# board_Two.net
KiCad netlist of a schematic drawn in Altium Designer
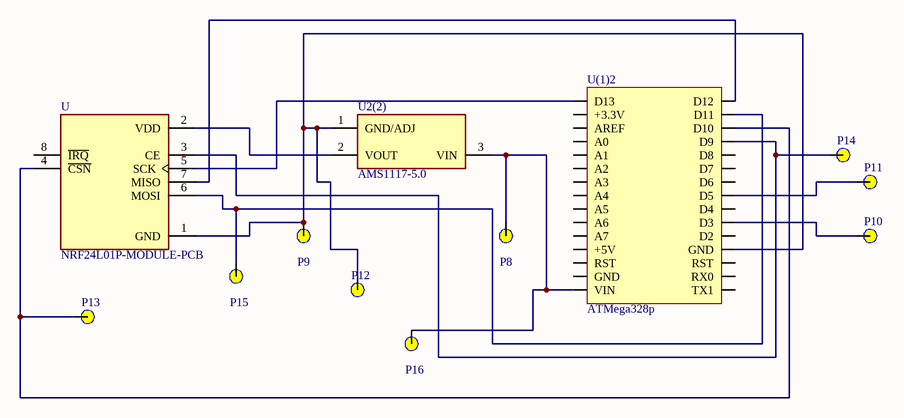
[diagram p0: board_Two.SchDoc]

(export (version "E")
  (design (tool "Eeschema 10.0.6"))
  (components
    (comp (ref "P8") (value "PIN_1") (footprint "PCB_Pin_1") (libsource (lib "Sch_Pin_1") (part "PIN_1")))
    (comp (ref "P9") (value "PIN_1") (footprint "PCB_Pin_1") (libsource (lib "Sch_Pin_1") (part "PIN_1")))
    (comp (ref "P10") (value "PIN_1") (footprint "PCB_Pin_1") (libsource (lib "Sch_Pin_1") (part "PIN_1")))
    (comp (ref "P11") (value "PIN_1") (footprint "PCB_Pin_1") (libsource (lib "Sch_Pin_1") (part "PIN_1")))
    (comp (ref "P12") (value "PIN_1") (footprint "PCB_Pin_1") (libsource (lib "") (part "PIN_1_1")))
    (comp (ref "P13") (value "PIN_1") (footprint "PCB_Pin_1") (libsource (lib "Sch_Pin_1") (part "PIN_1")))
    (comp (ref "P14") (value "PIN_1") (footprint "PCB_Pin_1") (libsource (lib "Sch_Pin_1") (part "PIN_1")))
    (comp (ref "P15") (value "PIN_1") (footprint "PCB_Pin_1") (libsource (lib "Sch_Pin_1") (part "PIN_1")))
    (comp (ref "P16") (value "PIN_1") (footprint "PCB_Pin_1") (libsource (lib "Sch_Pin_1") (part "PIN_1")))
    (comp (ref "U")
      (value "NRF24L01P-MODULE-PCB")
      (footprint "XCVR_NRF24L01P-MODULE-PCB")
      (description "- Transceiver For Use With nRF24L01+")
      (fields (field (name "MF") "Nordic Semiconductor"))
      (libsource (lib "NRF24L01P-MODULE-PCB") (part "NRF24L01P-MODULE-PCB"))
    )
    (comp (ref "U(1)2")
      (value "ATMega328p")
      (footprint "PCB_ATMega328p")
      (description "DCCduino Nano CH340 - аналог Arduino Nano v3.0 TYPE C")
      (libsource (lib "Sch_ATMega328p") (part "Arduino Nano"))
    )
    (comp (ref "U2(2)")
      (value "AMS1117-5.0")
      (footprint "SOT229P700X180-4N")
      (description "1A LOW DROPOUT VOLTAGE REGULATOR")
      (fields (field (name "MF") "ams"))
      (libsource (lib "AMS1117-3.3") (part "AMS1117-5.0"))
    )
  )
  (nets
    (net (code "1") (name "Net-(P10-Pin)") (class "Default")
      (node (ref "P10") (pin "0") (pinfunction "Pin_0") (pintype "passive"))
      (node (ref "U(1)2") (pin "24") (pinfunction "D3_24") (pintype "passive"))
    )
    (net (code "2") (name "Net-(P11-Pin)") (class "Default")
      (node (ref "P11") (pin "0") (pinfunction "Pin_0") (pintype "passive"))
      (node (ref "U(1)2") (pin "22") (pinfunction "D5_22") (pintype "passive"))
    )
    (net (code "3") (name "Net-(P12-Pin)") (class "Default")
      (node (ref "P12") (pin "0") (pinfunction "Pin_0") (pintype "passive"))
      (node (ref "P9") (pin "0") (pinfunction "Pin_0") (pintype "passive"))
      (node (ref "U") (pin "1") (pinfunction "GND_1") (pintype "power_in"))
      (node (ref "U(1)2") (pin "26") (pinfunction "GND_26") (pintype "passive"))
      (node (ref "U2(2)") (pin "1") (pinfunction "GND/ADJ_1") (pintype "power_in"))
    )
    (net (code "4") (name "Net-(P13-Pin)") (class "Default")
      (node (ref "P13") (pin "0") (pinfunction "Pin_0") (pintype "passive"))
      (node (ref "U") (pin "4") (pinfunction "~{CSN}_4") (pintype "power_in"))
      (node (ref "U(1)2") (pin "17") (pinfunction "D10_17") (pintype "passive"))
    )
    (net (code "5") (name "Net-(P14-Pin)") (class "Default")
      (node (ref "P14") (pin "0") (pinfunction "Pin_0") (pintype "passive"))
      (node (ref "U") (pin "3") (pinfunction "CE_3") (pintype "power_in"))
      (node (ref "U(1)2") (pin "18") (pinfunction "D9_18") (pintype "passive"))
    )
    (net (code "6") (name "Net-(P15-Pin)") (class "Default")
      (node (ref "P15") (pin "0") (pinfunction "Pin_0") (pintype "passive"))
      (node (ref "U") (pin "6") (pinfunction "MOSI_6") (pintype "power_in"))
      (node (ref "U(1)2") (pin "16") (pinfunction "D11_16") (pintype "passive"))
    )
    (net (code "7") (name "Net-(P16-Pin)") (class "Default")
      (node (ref "P16") (pin "0") (pinfunction "Pin_0") (pintype "passive"))
      (node (ref "P8") (pin "0") (pinfunction "Pin_0") (pintype "passive"))
      (node (ref "U(1)2") (pin "0") (pinfunction "VIN_0") (pintype "passive"))
      (node (ref "U2(2)") (pin "3") (pinfunction "VIN_3") (pintype "power_in"))
    )
    (net (code "8") (name "Net-(U(1)2-D12)") (class "Default")
      (node (ref "U") (pin "7") (pinfunction "MISO_7") (pintype "power_in"))
      (node (ref "U(1)2") (pin "15") (pinfunction "D12_15") (pintype "passive"))
    )
    (net (code "9") (name "Net-(U(1)2-D13)") (class "Default")
      (node (ref "U") (pin "5") (pinfunction "SCK_5") (pintype "power_in"))
      (node (ref "U(1)2") (pin "14") (pinfunction "D13_14") (pintype "passive"))
    )
    (net (code "10") (name "Net-(U-VDD)") (class "Default")
      (node (ref "U") (pin "2") (pinfunction "VDD_2") (pintype "power_in"))
      (node (ref "U2(2)") (pin "2") (pinfunction "VOUT_2") (pintype "power_in"))
    )
    (net (code "11") (name "unconnected-(U(1)2-+3.3V-Pad13)") (class "Default")
      (node (ref "U(1)2") (pin "13") (pinfunction "+3.3V_13") (pintype "passive"))
    )
    (net (code "12") (name "unconnected-(U(1)2-+5V-Pad3)") (class "Default")
      (node (ref "U(1)2") (pin "3") (pinfunction "+5V_3") (pintype "passive"))
    )
    (net (code "13") (name "unconnected-(U(1)2-A0-Pad11)") (class "Default")
      (node (ref "U(1)2") (pin "11") (pinfunction "A0_11") (pintype "passive"))
    )
    (net (code "14") (name "unconnected-(U(1)2-A1-Pad10)") (class "Default")
      (node (ref "U(1)2") (pin "10") (pinfunction "A1_10") (pintype "passive"))
    )
    (net (code "15") (name "unconnected-(U(1)2-A2-Pad9)") (class "Default")
      (node (ref "U(1)2") (pin "9") (pinfunction "A2_9") (pintype "passive"))
    )
    (net (code "16") (name "unconnected-(U(1)2-A3-Pad8)") (class "Default")
      (node (ref "U(1)2") (pin "8") (pinfunction "A3_8") (pintype "passive"))
    )
    (net (code "17") (name "unconnected-(U(1)2-A4-Pad7)") (class "Default")
      (node (ref "U(1)2") (pin "7") (pinfunction "A4_7") (pintype "passive"))
    )
    (net (code "18") (name "unconnected-(U(1)2-A5-Pad6)") (class "Default")
      (node (ref "U(1)2") (pin "6") (pinfunction "A5_6") (pintype "passive"))
    )
    (net (code "19") (name "unconnected-(U(1)2-A6-Pad5)") (class "Default")
      (node (ref "U(1)2") (pin "5") (pinfunction "A6_5") (pintype "passive"))
    )
    (net (code "20") (name "unconnected-(U(1)2-A7-Pad4)") (class "Default")
      (node (ref "U(1)2") (pin "4") (pinfunction "A7_4") (pintype "passive"))
    )
    (net (code "21") (name "unconnected-(U(1)2-AREF-Pad12)") (class "Default")
      (node (ref "U(1)2") (pin "12") (pinfunction "AREF_12") (pintype "passive"))
    )
    (net (code "22") (name "unconnected-(U(1)2-D2-Pad25)") (class "Default")
      (node (ref "U(1)2") (pin "25") (pinfunction "D2_25") (pintype "passive"))
    )
    (net (code "23") (name "unconnected-(U(1)2-D4-Pad23)") (class "Default")
      (node (ref "U(1)2") (pin "23") (pinfunction "D4_23") (pintype "passive"))
    )
    (net (code "24") (name "unconnected-(U(1)2-D6-Pad21)") (class "Default")
      (node (ref "U(1)2") (pin "21") (pinfunction "D6_21") (pintype "passive"))
    )
    (net (code "25") (name "unconnected-(U(1)2-D7-Pad20)") (class "Default")
      (node (ref "U(1)2") (pin "20") (pinfunction "D7_20") (pintype "passive"))
    )
    (net (code "26") (name "unconnected-(U(1)2-D8-Pad19)") (class "Default")
      (node (ref "U(1)2") (pin "19") (pinfunction "D8_19") (pintype "passive"))
    )
    (net (code "27") (name "unconnected-(U(1)2-GND-Pad1)") (class "Default")
      (node (ref "U(1)2") (pin "1") (pinfunction "GND_1") (pintype "passive"))
    )
    (net (code "28") (name "unconnected-(U(1)2-RST-Pad2)") (class "Default")
      (node (ref "U(1)2") (pin "2") (pinfunction "RST_2") (pintype "passive"))
    )
    (net (code "29") (name "unconnected-(U(1)2-RST-Pad27)") (class "Default")
      (node (ref "U(1)2") (pin "27") (pinfunction "RST_27") (pintype "passive"))
    )
    (net (code "30") (name "unconnected-(U(1)2-RX0-Pad28)") (class "Default")
      (node (ref "U(1)2") (pin "28") (pinfunction "RX0_28") (pintype "passive"))
    )
    (net (code "31") (name "unconnected-(U(1)2-TX1-Pad29)") (class "Default")
      (node (ref "U(1)2") (pin "29") (pinfunction "TX1_29") (pintype "passive"))
    )
    (net (code "32") (name "unconnected-(U-~{IRQ}-Pad8)") (class "Default")
      (node (ref "U") (pin "8") (pinfunction "~{IRQ}_8") (pintype "power_in"))
    )
  )
)
